# ALUprudente.net
KiCad netlist of a schematic drawn in EAGLE
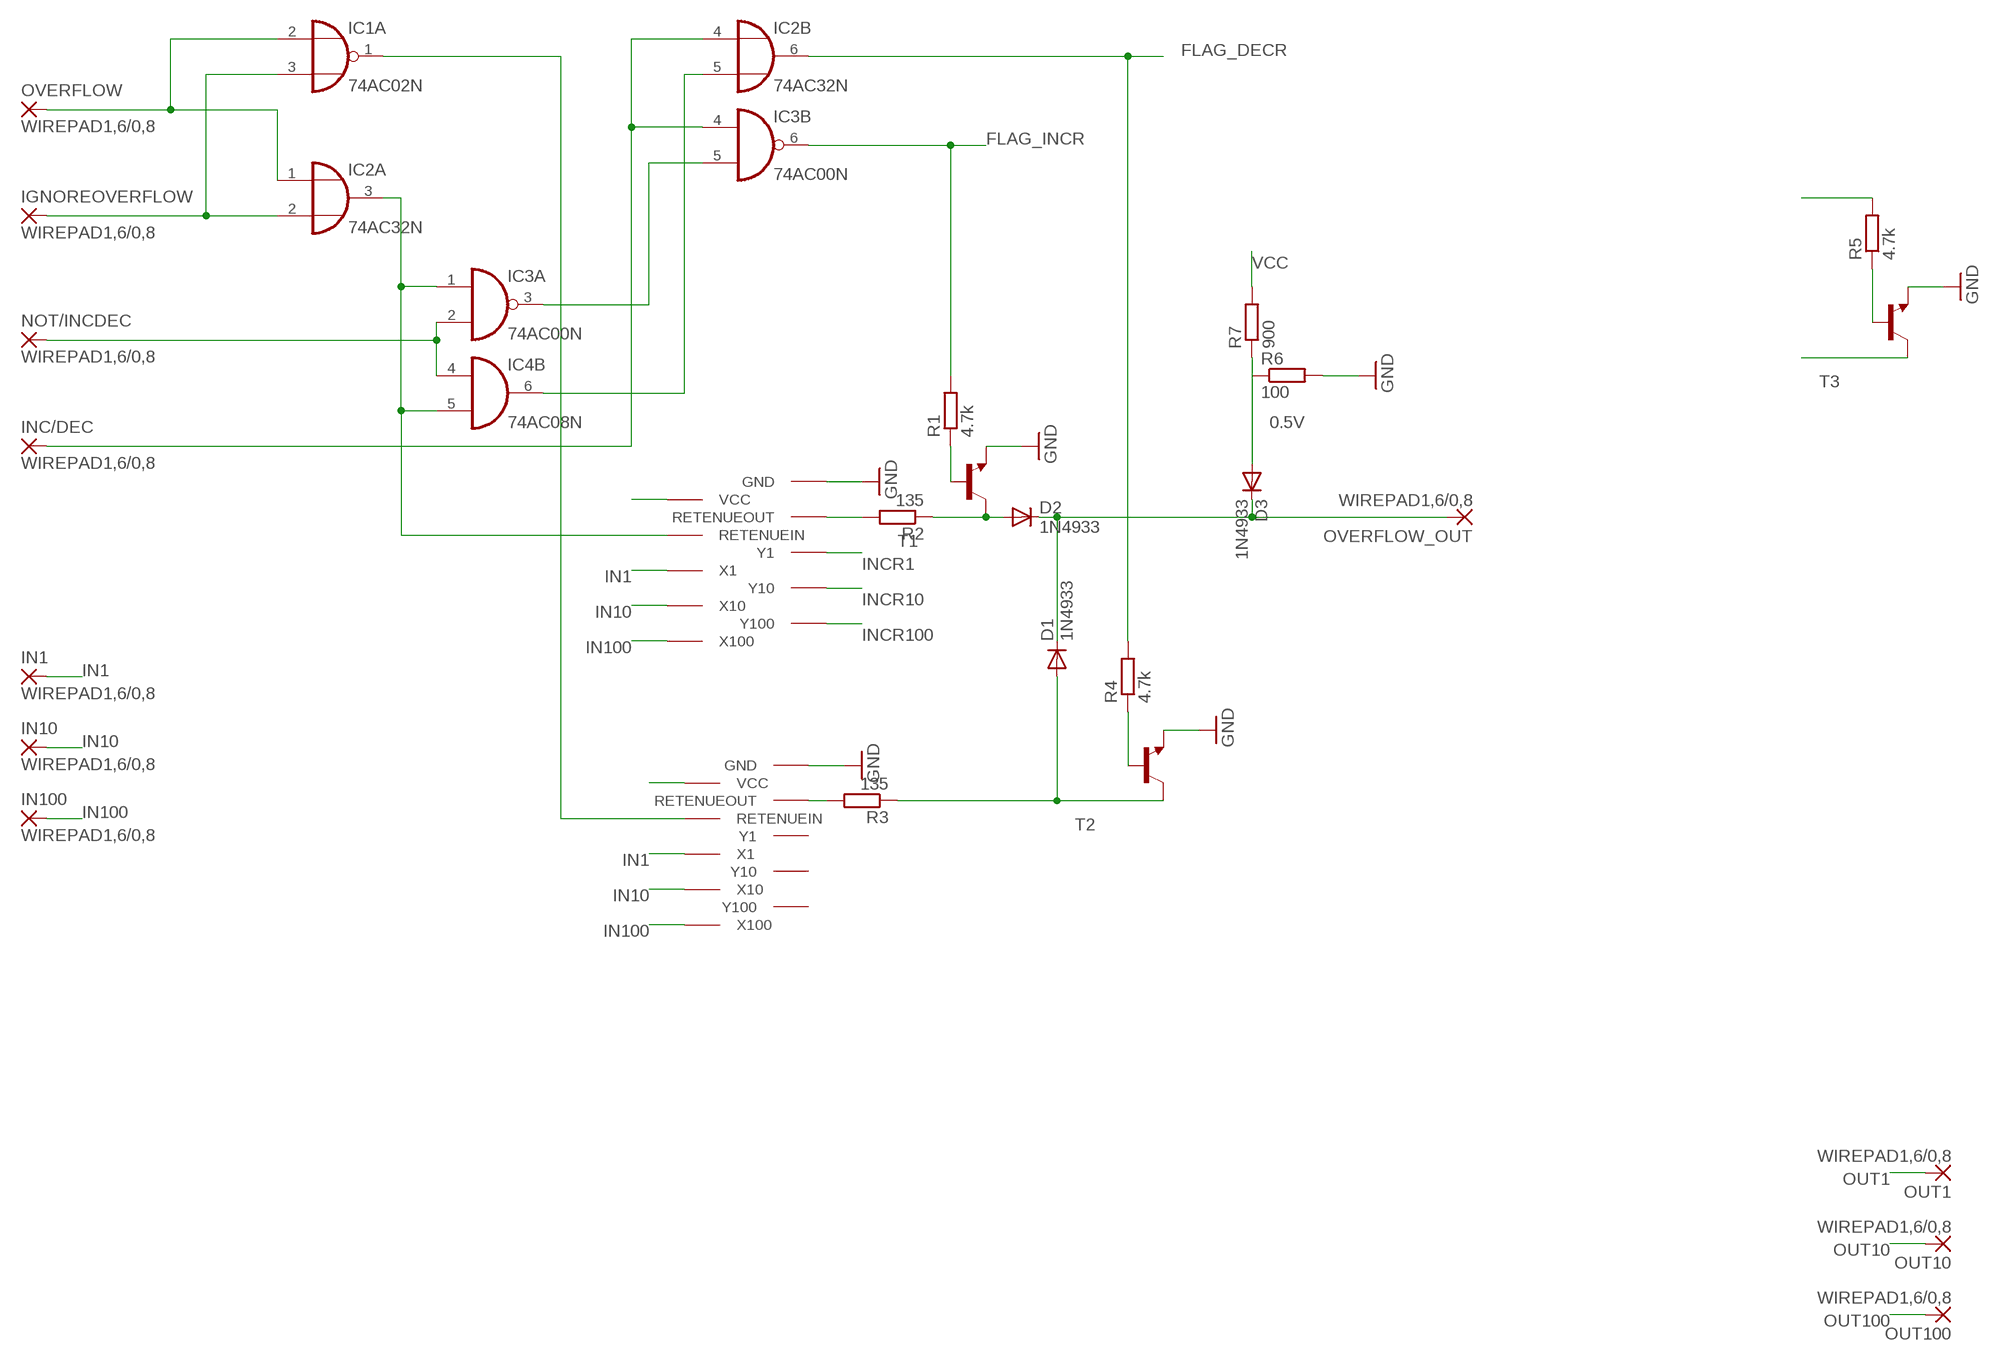
[diagram p0: schematic, sheet 1]

(export (version "E")
  (design (tool "Eeschema 10.0.6"))
  (components
    (comp (ref "D1")
      (value "1N4933")
      (footprint "eagle-import:DO41-10")
      (libsource (lib "eagle-import") (part "1N4933"))
    )
    (comp (ref "D2")
      (value "1N4933")
      (footprint "eagle-import:DO41-10")
      (libsource (lib "eagle-import") (part "1N4933"))
    )
    (comp (ref "D3")
      (value "1N4933")
      (footprint "eagle-import:DO41-10")
      (libsource (lib "eagle-import") (part "1N4933"))
    )
    (comp (ref "IC1")
      (value "74AC02N")
      (footprint "eagle-import:DIL14")
      (libsource (lib "eagle-import") (part "7402NAC"))
    )
    (comp (ref "IC2")
      (value "74AC32N")
      (footprint "eagle-import:DIL14")
      (libsource (lib "eagle-import") (part "7432NAC"))
    )
    (comp (ref "IC3")
      (value "74AC00N")
      (footprint "eagle-import:DIL14")
      (libsource (lib "eagle-import") (part "7400NAC"))
    )
    (comp (ref "IC4")
      (value "74AC08N")
      (footprint "eagle-import:DIL14")
      (libsource (lib "eagle-import") (part "7408NAC"))
    )
    (comp (ref "IGNOREOVERFLOW")
      (value "WIREPAD1,6/0,8")
      (footprint "eagle-import:1,6_0,8")
      (libsource (lib "eagle-import") (part "WIREPAD1,6/0,8"))
    )
    (comp (ref "IN1")
      (value "WIREPAD1,6/0,8")
      (footprint "eagle-import:1,6_0,8")
      (libsource (lib "eagle-import") (part "WIREPAD1,6/0,8"))
    )
    (comp (ref "IN10")
      (value "WIREPAD1,6/0,8")
      (footprint "eagle-import:1,6_0,8")
      (libsource (lib "eagle-import") (part "WIREPAD1,6/0,8"))
    )
    (comp (ref "IN100")
      (value "WIREPAD1,6/0,8")
      (footprint "eagle-import:1,6_0,8")
      (libsource (lib "eagle-import") (part "WIREPAD1,6/0,8"))
    )
    (comp (ref "INC/DEC")
      (value "WIREPAD1,6/0,8")
      (footprint "eagle-import:1,6_0,8")
      (libsource (lib "eagle-import") (part "WIREPAD1,6/0,8"))
    )
    (comp (ref "NOT/INCDEC")
      (value "WIREPAD1,6/0,8")
      (footprint "eagle-import:1,6_0,8")
      (libsource (lib "eagle-import") (part "WIREPAD1,6/0,8"))
    )
    (comp (ref "OUT1")
      (value "WIREPAD1,6/0,8")
      (footprint "eagle-import:1,6_0,8")
      (libsource (lib "eagle-import") (part "WIREPAD1,6/0,8"))
    )
    (comp (ref "OUT10")
      (value "WIREPAD1,6/0,8")
      (footprint "eagle-import:1,6_0,8")
      (libsource (lib "eagle-import") (part "WIREPAD1,6/0,8"))
    )
    (comp (ref "OUT100")
      (value "WIREPAD1,6/0,8")
      (footprint "eagle-import:1,6_0,8")
      (libsource (lib "eagle-import") (part "WIREPAD1,6/0,8"))
    )
    (comp (ref "OVERFLOW")
      (value "WIREPAD1,6/0,8")
      (footprint "eagle-import:1,6_0,8")
      (libsource (lib "eagle-import") (part "WIREPAD1,6/0,8"))
    )
    (comp (ref "OVERFLOW_OUT")
      (value "WIREPAD1,6/0,8")
      (footprint "eagle-import:1,6_0,8")
      (libsource (lib "eagle-import") (part "WIREPAD1,6/0,8"))
    )
    (comp (ref "R1")
      (value "4.7k")
      (footprint "eagle-import:0309_10")
      (libsource (lib "eagle-import") (part "R-EU_0309/10"))
    )
    (comp (ref "R2")
      (value "135")
      (footprint "eagle-import:0309_10")
      (libsource (lib "eagle-import") (part "R-EU_0309/10"))
    )
    (comp (ref "R3")
      (value "135")
      (footprint "eagle-import:0309_10")
      (libsource (lib "eagle-import") (part "R-EU_0309/10"))
    )
    (comp (ref "R4")
      (value "4.7k")
      (footprint "eagle-import:0309_10")
      (libsource (lib "eagle-import") (part "R-EU_0309/10"))
    )
    (comp (ref "R5")
      (value "4.7k")
      (footprint "eagle-import:0309_10")
      (libsource (lib "eagle-import") (part "R-EU_0309/10"))
    )
    (comp (ref "R6")
      (value "100")
      (footprint "eagle-import:0309_10")
      (libsource (lib "eagle-import") (part "R-EU_0309/10"))
    )
    (comp (ref "R7")
      (value "900")
      (footprint "eagle-import:0309_10")
      (libsource (lib "eagle-import") (part "R-EU_0309/10"))
    )
    (comp (ref "T1")
      (value "BC637-NPN-TO92-ECB")
      (footprint "eagle-import:TO92-ECB")
      (libsource (lib "eagle-import") (part "-NPN-TO92-ECBBC637"))
    )
    (comp (ref "T2")
      (value "BC637-NPN-TO92-ECB")
      (footprint "eagle-import:TO92-ECB")
      (libsource (lib "eagle-import") (part "-NPN-TO92-ECBBC637"))
    )
    (comp (ref "T3")
      (value "BC637-NPN-TO92-ECB")
      (footprint "eagle-import:TO92-ECB")
      (libsource (lib "eagle-import") (part "-NPN-TO92-ECBBC637"))
    )
    (comp (ref "U$1")
      (value "INCR3B")
      (footprint "eagle-import:INCR3B")
      (libsource (lib "eagle-import") (part "INCR3B"))
    )
    (comp (ref "U$2")
      (value "DECR3B")
      (footprint "eagle-import:DECR3B")
      (libsource (lib "eagle-import") (part "DECR3B"))
    )
  )
  (nets
    (net (code "1") (name "/0.5V") (class "Default")
      (node (ref "D3") (pin "A") (pinfunction "A_A") (pintype "passive"))
      (node (ref "R7") (pin "1") (pinfunction "1_1") (pintype "passive"))
    )
    (net (code "2") (name "/FLAG_DECR") (class "Default")
      (node (ref "IC2") (pin "6") (pinfunction "O_6") (pintype "output"))
      (node (ref "R4") (pin "2") (pinfunction "2_2") (pintype "passive"))
    )
    (net (code "3") (name "/FLAG_INCR") (class "Default")
      (node (ref "IC3") (pin "6") (pinfunction "O_6") (pintype "output"))
      (node (ref "R1") (pin "2") (pinfunction "2_2") (pintype "passive"))
    )
    (net (code "4") (name "/IN1") (class "Default")
      (node (ref "IN1") (pin "1") (pinfunction "P_1") (pintype "passive"))
      (node (ref "U$1") (pin "X1") (pinfunction "X1_X1") (pintype "bidirectional"))
      (node (ref "U$2") (pin "X1") (pinfunction "X1_X1") (pintype "bidirectional"))
    )
    (net (code "5") (name "/IN10") (class "Default")
      (node (ref "IN10") (pin "1") (pinfunction "P_1") (pintype "passive"))
      (node (ref "U$1") (pin "X10") (pinfunction "X10_X10") (pintype "bidirectional"))
      (node (ref "U$2") (pin "X10") (pinfunction "X10_X10") (pintype "bidirectional"))
    )
    (net (code "6") (name "/IN100") (class "Default")
      (node (ref "IN100") (pin "1") (pinfunction "P_1") (pintype "passive"))
      (node (ref "U$1") (pin "X100") (pinfunction "X100_X100") (pintype "bidirectional"))
      (node (ref "U$2") (pin "X100") (pinfunction "X100_X100") (pintype "bidirectional"))
    )
    (net (code "7") (name "/INCR1") (class "Default")
      (node (ref "U$1") (pin "Y1") (pinfunction "Y1_Y1") (pintype "bidirectional"))
    )
    (net (code "8") (name "/INCR10") (class "Default")
      (node (ref "U$1") (pin "Y10") (pinfunction "Y10_Y10") (pintype "bidirectional"))
    )
    (net (code "9") (name "/INCR100") (class "Default")
      (node (ref "U$1") (pin "Y100") (pinfunction "Y100_Y100") (pintype "bidirectional"))
    )
    (net (code "10") (name "/OUT1") (class "Default")
      (node (ref "OUT1") (pin "1") (pinfunction "P_1") (pintype "passive"))
    )
    (net (code "11") (name "/OUT10") (class "Default")
      (node (ref "OUT10") (pin "1") (pinfunction "P_1") (pintype "passive"))
    )
    (net (code "12") (name "/OUT100") (class "Default")
      (node (ref "OUT100") (pin "1") (pinfunction "P_1") (pintype "passive"))
    )
    (net (code "13") (name "/VCC") (class "Default")
      (node (ref "R7") (pin "2") (pinfunction "2_2") (pintype "passive"))
      (node (ref "U$1") (pin "VCC") (pinfunction "VCC_VCC") (pintype "bidirectional"))
      (node (ref "U$2") (pin "VCC") (pinfunction "VCC_VCC") (pintype "bidirectional"))
    )
    (net (code "14") (name "GND") (class "Default")
      (node (ref "R6") (pin "2") (pinfunction "2_2") (pintype "passive"))
      (node (ref "T1") (pin "E") (pinfunction "E_E") (pintype "passive"))
      (node (ref "T2") (pin "E") (pinfunction "E_E") (pintype "passive"))
      (node (ref "T3") (pin "E") (pinfunction "E_E") (pintype "passive"))
      (node (ref "U$1") (pin "GND") (pinfunction "GND_GND") (pintype "bidirectional"))
      (node (ref "U$2") (pin "GND") (pinfunction "GND_GND") (pintype "bidirectional"))
    )
    (net (code "15") (name "Net-(D1-PadA)") (class "Default")
      (node (ref "D1") (pin "A") (pinfunction "A_A") (pintype "passive"))
      (node (ref "R3") (pin "1") (pinfunction "1_1") (pintype "passive"))
      (node (ref "T2") (pin "C") (pinfunction "C_C") (pintype "passive"))
    )
    (net (code "16") (name "Net-(D2-PadA)") (class "Default")
      (node (ref "D2") (pin "A") (pinfunction "A_A") (pintype "passive"))
      (node (ref "R2") (pin "1") (pinfunction "1_1") (pintype "passive"))
      (node (ref "T1") (pin "C") (pinfunction "C_C") (pintype "passive"))
    )
    (net (code "17") (name "Net-(IC1A-I0)") (class "Default")
      (node (ref "IC1") (pin "2") (pinfunction "I0_2") (pintype "input"))
      (node (ref "IC2") (pin "1") (pinfunction "I0_1") (pintype "input"))
      (node (ref "OVERFLOW") (pin "1") (pinfunction "P_1") (pintype "passive"))
    )
    (net (code "18") (name "Net-(IC1A-I1)") (class "Default")
      (node (ref "IC1") (pin "3") (pinfunction "I1_3") (pintype "input"))
      (node (ref "IC2") (pin "2") (pinfunction "I1_2") (pintype "input"))
      (node (ref "IGNOREOVERFLOW") (pin "1") (pinfunction "P_1") (pintype "passive"))
    )
    (net (code "19") (name "Net-(IC1A-O)") (class "Default")
      (node (ref "IC1") (pin "1") (pinfunction "O_1") (pintype "output"))
      (node (ref "U$2") (pin "RETENUEIN") (pinfunction "RETENUEIN_RETENUEIN") (pintype "bidirectional"))
    )
    (net (code "20") (name "Net-(IC2A-O)") (class "Default")
      (node (ref "IC2") (pin "3") (pinfunction "O_3") (pintype "output"))
      (node (ref "IC3") (pin "1") (pinfunction "I0_1") (pintype "input"))
      (node (ref "IC4") (pin "5") (pinfunction "I1_5") (pintype "input"))
      (node (ref "U$1") (pin "RETENUEIN") (pinfunction "RETENUEIN_RETENUEIN") (pintype "bidirectional"))
    )
    (net (code "21") (name "Net-(IC2B-I0)") (class "Default")
      (node (ref "IC2") (pin "4") (pinfunction "I0_4") (pintype "input"))
      (node (ref "IC3") (pin "4") (pinfunction "I0_4") (pintype "input"))
      (node (ref "INC/DEC") (pin "1") (pinfunction "P_1") (pintype "passive"))
    )
    (net (code "22") (name "Net-(IC2B-I1)") (class "Default")
      (node (ref "IC2") (pin "5") (pinfunction "I1_5") (pintype "input"))
      (node (ref "IC4") (pin "6") (pinfunction "O_6") (pintype "output"))
    )
    (net (code "23") (name "Net-(IC3A-I1)") (class "Default")
      (node (ref "IC3") (pin "2") (pinfunction "I1_2") (pintype "input"))
      (node (ref "IC4") (pin "4") (pinfunction "I0_4") (pintype "input"))
      (node (ref "NOT/INCDEC") (pin "1") (pinfunction "P_1") (pintype "passive"))
    )
    (net (code "24") (name "Net-(IC3A-O)") (class "Default")
      (node (ref "IC3") (pin "3") (pinfunction "O_3") (pintype "output"))
      (node (ref "IC3") (pin "5") (pinfunction "I1_5") (pintype "input"))
    )
    (net (code "25") (name "Net-(OVERFLOW_OUT-P)") (class "Default")
      (node (ref "D1") (pin "C") (pinfunction "C_C") (pintype "passive"))
      (node (ref "D2") (pin "C") (pinfunction "C_C") (pintype "passive"))
      (node (ref "D3") (pin "C") (pinfunction "C_C") (pintype "passive"))
      (node (ref "OVERFLOW_OUT") (pin "1") (pinfunction "P_1") (pintype "passive"))
    )
    (net (code "26") (name "Net-(R1-Pad1)") (class "Default")
      (node (ref "R1") (pin "1") (pinfunction "1_1") (pintype "passive"))
      (node (ref "T1") (pin "B") (pinfunction "B_B") (pintype "passive"))
    )
    (net (code "27") (name "Net-(R2-Pad2)") (class "Default")
      (node (ref "R2") (pin "2") (pinfunction "2_2") (pintype "passive"))
      (node (ref "U$1") (pin "RETENUEOUT") (pinfunction "RETENUEOUT_RETENUEOUT") (pintype "bidirectional"))
    )
    (net (code "28") (name "Net-(R3-Pad2)") (class "Default")
      (node (ref "R3") (pin "2") (pinfunction "2_2") (pintype "passive"))
      (node (ref "U$2") (pin "RETENUEOUT") (pinfunction "RETENUEOUT_RETENUEOUT") (pintype "bidirectional"))
    )
    (net (code "29") (name "Net-(R4-Pad1)") (class "Default")
      (node (ref "R4") (pin "1") (pinfunction "1_1") (pintype "passive"))
      (node (ref "T2") (pin "B") (pinfunction "B_B") (pintype "passive"))
    )
    (net (code "30") (name "Net-(R5-Pad1)") (class "Default")
      (node (ref "R5") (pin "1") (pinfunction "1_1") (pintype "passive"))
      (node (ref "T3") (pin "B") (pinfunction "B_B") (pintype "passive"))
    )
    (net (code "31") (name "unconnected-(R5-Pad2)") (class "Default")
      (node (ref "R5") (pin "2") (pinfunction "2_2") (pintype "passive"))
    )
    (net (code "32") (name "unconnected-(R6-Pad1)") (class "Default")
      (node (ref "R6") (pin "1") (pinfunction "1_1") (pintype "passive"))
    )
    (net (code "33") (name "unconnected-(T3-PadC)") (class "Default")
      (node (ref "T3") (pin "C") (pinfunction "C_C") (pintype "passive"))
    )
    (net (code "34") (name "unconnected-(U$2-PadY1)") (class "Default")
      (node (ref "U$2") (pin "Y1") (pinfunction "Y1_Y1") (pintype "bidirectional"))
    )
    (net (code "35") (name "unconnected-(U$2-PadY10)") (class "Default")
      (node (ref "U$2") (pin "Y10") (pinfunction "Y10_Y10") (pintype "bidirectional"))
    )
    (net (code "36") (name "unconnected-(U$2-PadY100)") (class "Default")
      (node (ref "U$2") (pin "Y100") (pinfunction "Y100_Y100") (pintype "bidirectional"))
    )
  )
)
